# Super-Regenerative-Receiver-1Transistor-.net
KiCad netlist of a schematic drawn in EAGLE
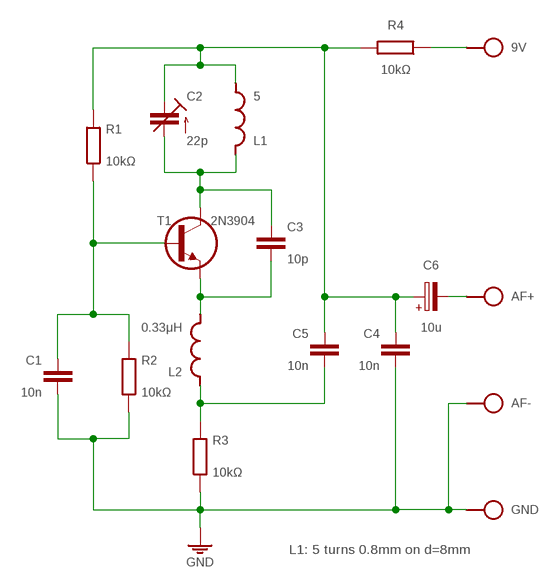
[diagram p0: schematic, sheet 1]

(export (version "E")
  (design (tool "Eeschema 10.0.6"))
  (components
    (comp (ref "9V")
      (value "SPAD")
      (footprint "eagle-import:SPAD")
      (libsource (lib "eagle-import") (part "SPAD"))
    )
    (comp (ref "AF+")
      (value "SPAD")
      (footprint "eagle-import:SPAD")
      (libsource (lib "eagle-import") (part "SPAD"))
    )
    (comp (ref "AF-")
      (value "SPAD")
      (footprint "eagle-import:SPAD")
      (libsource (lib "eagle-import") (part "SPAD"))
    )
    (comp (ref "C1")
      (value "10n")
      (footprint "eagle-import:C050-020X036_V")
      (libsource (lib "eagle-import") (part "C050-020X036/V"))
    )
    (comp (ref "C2")
      (value "22p")
      (footprint "eagle-import:TRIM-2222-808")
      (libsource (lib "eagle-import") (part "C-TR-PH20127"))
    )
    (comp (ref "C3")
      (value "10p")
      (footprint "eagle-import:C050-020X036_V")
      (libsource (lib "eagle-import") (part "C050-020X036/V"))
    )
    (comp (ref "C4")
      (value "10n")
      (footprint "eagle-import:C050-020X036_V")
      (libsource (lib "eagle-import") (part "C050-020X036/V"))
    )
    (comp (ref "C5")
      (value "10n")
      (footprint "eagle-import:C050-020X036_V")
      (libsource (lib "eagle-import") (part "C050-020X036/V"))
    )
    (comp (ref "C6")
      (value "10u")
      (footprint "eagle-import:E2,5-3")
      (libsource (lib "eagle-import") (part "CPOLE2,5-3"))
    )
    (comp (ref "GND")
      (value "SPAD")
      (footprint "eagle-import:SPAD")
      (libsource (lib "eagle-import") (part "SPAD"))
    )
    (comp (ref "L1")
      (value "5")
      (footprint "eagle-import:L-04-5_5V-X")
      (libsource (lib "eagle-import") (part "L-SHORTL-04-5/5V-X"))
    )
    (comp (ref "L2")
      (value "0.33μH")
      (footprint "eagle-import:L-02_7V")
      (libsource (lib "eagle-import") (part "L-SHORT02/7V"))
    )
    (comp (ref "R1")
      (value "10kΩ")
      (footprint "eagle-import:0204_10")
      (libsource (lib "eagle-import") (part "R0204/10"))
    )
    (comp (ref "R2")
      (value "10kΩ")
      (footprint "eagle-import:0204_10")
      (libsource (lib "eagle-import") (part "R0204/10"))
    )
    (comp (ref "R3")
      (value "10kΩ")
      (footprint "eagle-import:0204_10")
      (libsource (lib "eagle-import") (part "R0204/10"))
    )
    (comp (ref "R4")
      (value "10kΩ")
      (footprint "eagle-import:0204_7")
      (libsource (lib "eagle-import") (part "R0204/7"))
    )
    (comp (ref "T1")
      (value "2N3904")
      (footprint "eagle-import:TO92")
      (libsource (lib "eagle-import") (part "2N3904"))
    )
  )
  (nets
    (net (code "1") (name "GND") (class "Default")
      (node (ref "AF-") (pin "1") (pinfunction "P$1_1") (pintype "passive"))
      (node (ref "C1") (pin "2") (pinfunction "2_2") (pintype "passive"))
      (node (ref "C4") (pin "2") (pinfunction "2_2") (pintype "passive"))
      (node (ref "GND") (pin "1") (pinfunction "P$1_1") (pintype "passive"))
      (node (ref "R2") (pin "1") (pinfunction "1_1") (pintype "passive"))
      (node (ref "R3") (pin "1") (pinfunction "1_1") (pintype "passive"))
    )
    (net (code "2") (name "Net-(9V-P$1)") (class "Default")
      (node (ref "9V") (pin "1") (pinfunction "P$1_1") (pintype "passive"))
      (node (ref "R4") (pin "1") (pinfunction "1_1") (pintype "passive"))
    )
    (net (code "3") (name "Net-(AF+-P$1)") (class "Default")
      (node (ref "AF+") (pin "1") (pinfunction "P$1_1") (pintype "passive"))
      (node (ref "C6") (pin "-") (pinfunction "-_-") (pintype "passive"))
    )
    (net (code "4") (name "Net-(C2-A)") (class "Default")
      (node (ref "C2") (pin "2") (pinfunction "A_2") (pintype "passive"))
      (node (ref "C3") (pin "1") (pinfunction "1_1") (pintype "passive"))
      (node (ref "L1") (pin "2") (pinfunction "2_2") (pintype "passive"))
      (node (ref "T1") (pin "3") (pinfunction "C_3") (pintype "passive"))
    )
    (net (code "5") (name "Net-(C2-E-Pad1)") (class "Default")
      (node (ref "C2") (pin "1") (pinfunction "E_1") (pintype "passive"))
      (node (ref "C2") (pin "3") (pinfunction "E_3") (pintype "passive"))
      (node (ref "C4") (pin "1") (pinfunction "1_1") (pintype "passive"))
      (node (ref "C5") (pin "1") (pinfunction "1_1") (pintype "passive"))
      (node (ref "C6") (pin "+") (pinfunction "+_+") (pintype "passive"))
      (node (ref "L1") (pin "1") (pinfunction "1_1") (pintype "passive"))
      (node (ref "R1") (pin "2") (pinfunction "2_2") (pintype "passive"))
      (node (ref "R4") (pin "2") (pinfunction "2_2") (pintype "passive"))
    )
    (net (code "6") (name "Net-(C5-Pad2)") (class "Default")
      (node (ref "C5") (pin "2") (pinfunction "2_2") (pintype "passive"))
      (node (ref "L2") (pin "2") (pinfunction "2_2") (pintype "passive"))
      (node (ref "R3") (pin "2") (pinfunction "2_2") (pintype "passive"))
    )
    (net (code "7") (name "Net-(T1-B)") (class "Default")
      (node (ref "C1") (pin "1") (pinfunction "1_1") (pintype "passive"))
      (node (ref "R1") (pin "1") (pinfunction "1_1") (pintype "passive"))
      (node (ref "R2") (pin "2") (pinfunction "2_2") (pintype "passive"))
      (node (ref "T1") (pin "2") (pinfunction "B_2") (pintype "passive"))
    )
    (net (code "8") (name "Net-(T1-E)") (class "Default")
      (node (ref "C3") (pin "2") (pinfunction "2_2") (pintype "passive"))
      (node (ref "L2") (pin "1") (pinfunction "1_1") (pintype "passive"))
      (node (ref "T1") (pin "1") (pinfunction "E_1") (pintype "passive"))
    )
  )
)
